# tweeq_stamp_9DOF.net
KiCad netlist of a schematic drawn in EAGLE
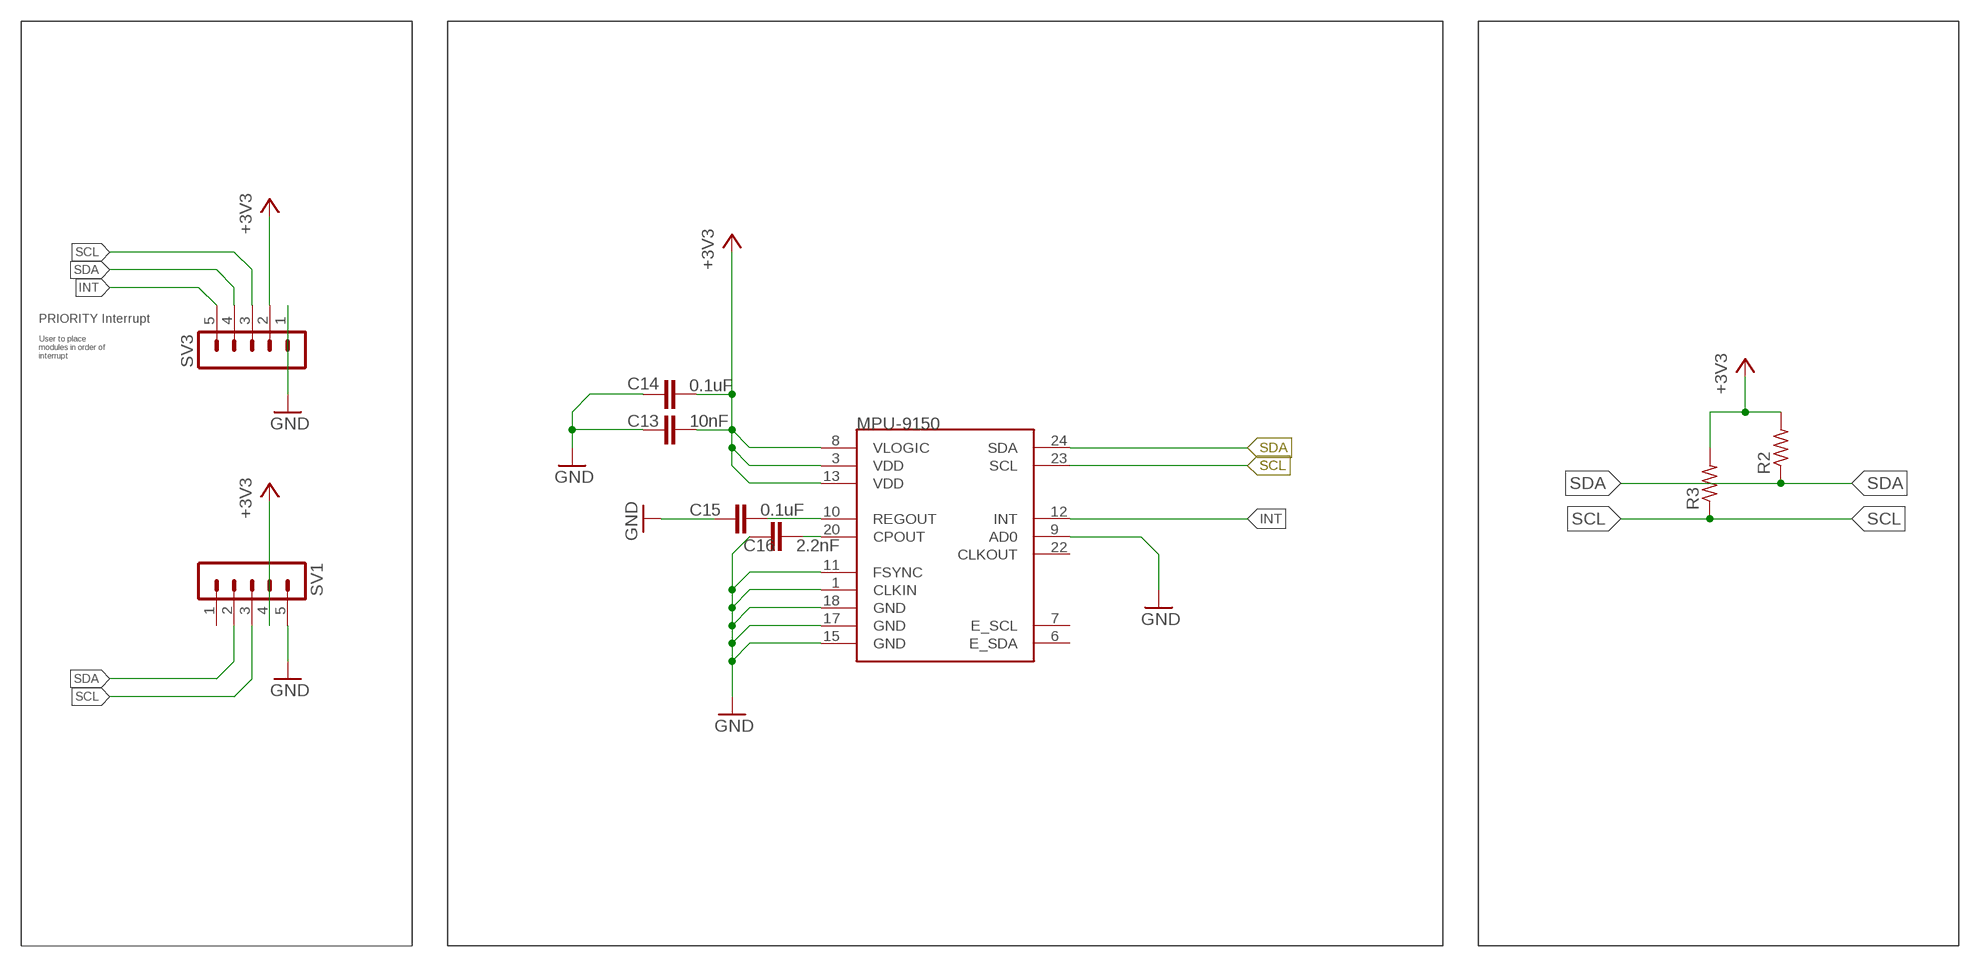
[diagram p0: schematic, sheet 1]

(export (version "E")
  (design (tool "Eeschema 10.0.6"))
  (components
    (comp (ref "C13")
      (value "10nF")
      (footprint "eagle-import:C0402K")
      (libsource (lib "eagle-import") (part "C-EUC0402K"))
    )
    (comp (ref "C14")
      (value "0.1uF")
      (footprint "eagle-import:C0402K")
      (libsource (lib "eagle-import") (part "C-EUC0402K"))
    )
    (comp (ref "C15")
      (value "0.1uF")
      (footprint "eagle-import:C0402K")
      (libsource (lib "eagle-import") (part "C-EUC0402K"))
    )
    (comp (ref "C16")
      (value "2.2nF")
      (footprint "eagle-import:C0402K")
      (libsource (lib "eagle-import") (part "C-EUC0402K"))
    )
    (comp (ref "MPU-9150")
      (value "MPU-9150QFN-24-NP")
      (footprint "eagle-import:QFN-24-NP")
      (libsource (lib "eagle-import") (part "MPU-9150QFN-24-NP"))
    )
    (comp (ref "R2")
      (value "R-US_R0402")
      (footprint "eagle-import:R0402")
      (libsource (lib "eagle-import") (part "R-US_R0402"))
    )
    (comp (ref "R3")
      (value "R-US_R0402")
      (footprint "eagle-import:R0402")
      (libsource (lib "eagle-import") (part "R-US_R0402"))
    )
    (comp (ref "SV1")
      (value "M05-1STAMP")
      (footprint "eagle-import:1X05-1.5MM-STAMP")
      (libsource (lib "eagle-import") (part "M05-1STAMP"))
    )
    (comp (ref "SV3")
      (value "M05-1STAMP")
      (footprint "eagle-import:1X05-1.5MM-STAMP")
      (libsource (lib "eagle-import") (part "M05-1STAMP"))
    )
  )
  (nets
    (net (code "1") (name "+3V3") (class "Default")
      (node (ref "C13") (pin "2") (pinfunction "2_2") (pintype "passive"))
      (node (ref "C14") (pin "2") (pinfunction "2_2") (pintype "passive"))
      (node (ref "MPU-9150") (pin "13") (pinfunction "VDD_13") (pintype "bidirectional"))
      (node (ref "MPU-9150") (pin "3") (pinfunction "VDD_3") (pintype "bidirectional"))
      (node (ref "MPU-9150") (pin "8") (pinfunction "VLOGIC_8") (pintype "bidirectional"))
      (node (ref "R2") (pin "2") (pinfunction "2_2") (pintype "passive"))
      (node (ref "R3") (pin "2") (pinfunction "2_2") (pintype "passive"))
      (node (ref "SV1") (pin "4") (pinfunction "4_4") (pintype "passive"))
      (node (ref "SV3") (pin "2") (pinfunction "2_2") (pintype "passive"))
    )
    (net (code "2") (name "GND") (class "Default")
      (node (ref "C13") (pin "1") (pinfunction "1_1") (pintype "passive"))
      (node (ref "C14") (pin "1") (pinfunction "1_1") (pintype "passive"))
      (node (ref "C15") (pin "1") (pinfunction "1_1") (pintype "passive"))
      (node (ref "C16") (pin "1") (pinfunction "1_1") (pintype "passive"))
      (node (ref "MPU-9150") (pin "1") (pinfunction "CLKIN_1") (pintype "bidirectional"))
      (node (ref "MPU-9150") (pin "11") (pinfunction "FSYNC_11") (pintype "bidirectional"))
      (node (ref "MPU-9150") (pin "15") (pinfunction "GND_15") (pintype "bidirectional"))
      (node (ref "MPU-9150") (pin "17") (pinfunction "GND_17") (pintype "bidirectional"))
      (node (ref "MPU-9150") (pin "18") (pinfunction "GND_18") (pintype "bidirectional"))
      (node (ref "MPU-9150") (pin "9") (pinfunction "AD0_9") (pintype "bidirectional"))
      (node (ref "SV1") (pin "5") (pinfunction "5_5") (pintype "passive"))
      (node (ref "SV3") (pin "1") (pinfunction "1_1") (pintype "passive"))
    )
    (net (code "3") (name "INT") (class "Default")
      (node (ref "MPU-9150") (pin "12") (pinfunction "INT_12") (pintype "bidirectional"))
      (node (ref "SV3") (pin "5") (pinfunction "5_5") (pintype "passive"))
    )
    (net (code "4") (name "Net-(MPU-9150-CPOUT)") (class "Default")
      (node (ref "C16") (pin "2") (pinfunction "2_2") (pintype "passive"))
      (node (ref "MPU-9150") (pin "20") (pinfunction "CPOUT_20") (pintype "bidirectional"))
    )
    (net (code "5") (name "Net-(MPU-9150-REGOUT)") (class "Default")
      (node (ref "C15") (pin "2") (pinfunction "2_2") (pintype "passive"))
      (node (ref "MPU-9150") (pin "10") (pinfunction "REGOUT_10") (pintype "bidirectional"))
    )
    (net (code "6") (name "SCL") (class "Default")
      (node (ref "MPU-9150") (pin "23") (pinfunction "SCL_23") (pintype "bidirectional"))
      (node (ref "R3") (pin "1") (pinfunction "1_1") (pintype "passive"))
      (node (ref "SV1") (pin "3") (pinfunction "3_3") (pintype "passive"))
      (node (ref "SV3") (pin "3") (pinfunction "3_3") (pintype "passive"))
    )
    (net (code "7") (name "SDA") (class "Default")
      (node (ref "MPU-9150") (pin "24") (pinfunction "SDA_24") (pintype "bidirectional"))
      (node (ref "R2") (pin "1") (pinfunction "1_1") (pintype "passive"))
      (node (ref "SV1") (pin "2") (pinfunction "2_2") (pintype "passive"))
      (node (ref "SV3") (pin "4") (pinfunction "4_4") (pintype "passive"))
    )
    (net (code "8") (name "unconnected-(MPU-9150-CLKOUT-Pad22)") (class "Default")
      (node (ref "MPU-9150") (pin "22") (pinfunction "CLKOUT_22") (pintype "bidirectional"))
    )
    (net (code "9") (name "unconnected-(MPU-9150-E_SCL-Pad7)") (class "Default")
      (node (ref "MPU-9150") (pin "7") (pinfunction "E_SCL_7") (pintype "bidirectional"))
    )
    (net (code "10") (name "unconnected-(MPU-9150-E_SDA-Pad6)") (class "Default")
      (node (ref "MPU-9150") (pin "6") (pinfunction "E_SDA_6") (pintype "bidirectional"))
    )
    (net (code "11") (name "unconnected-(SV1-Pad1)") (class "Default")
      (node (ref "SV1") (pin "1") (pinfunction "1_1") (pintype "passive"))
    )
  )
)
